# AlmosFinalMC.net
KiCad netlist of a schematic drawn in EAGLE
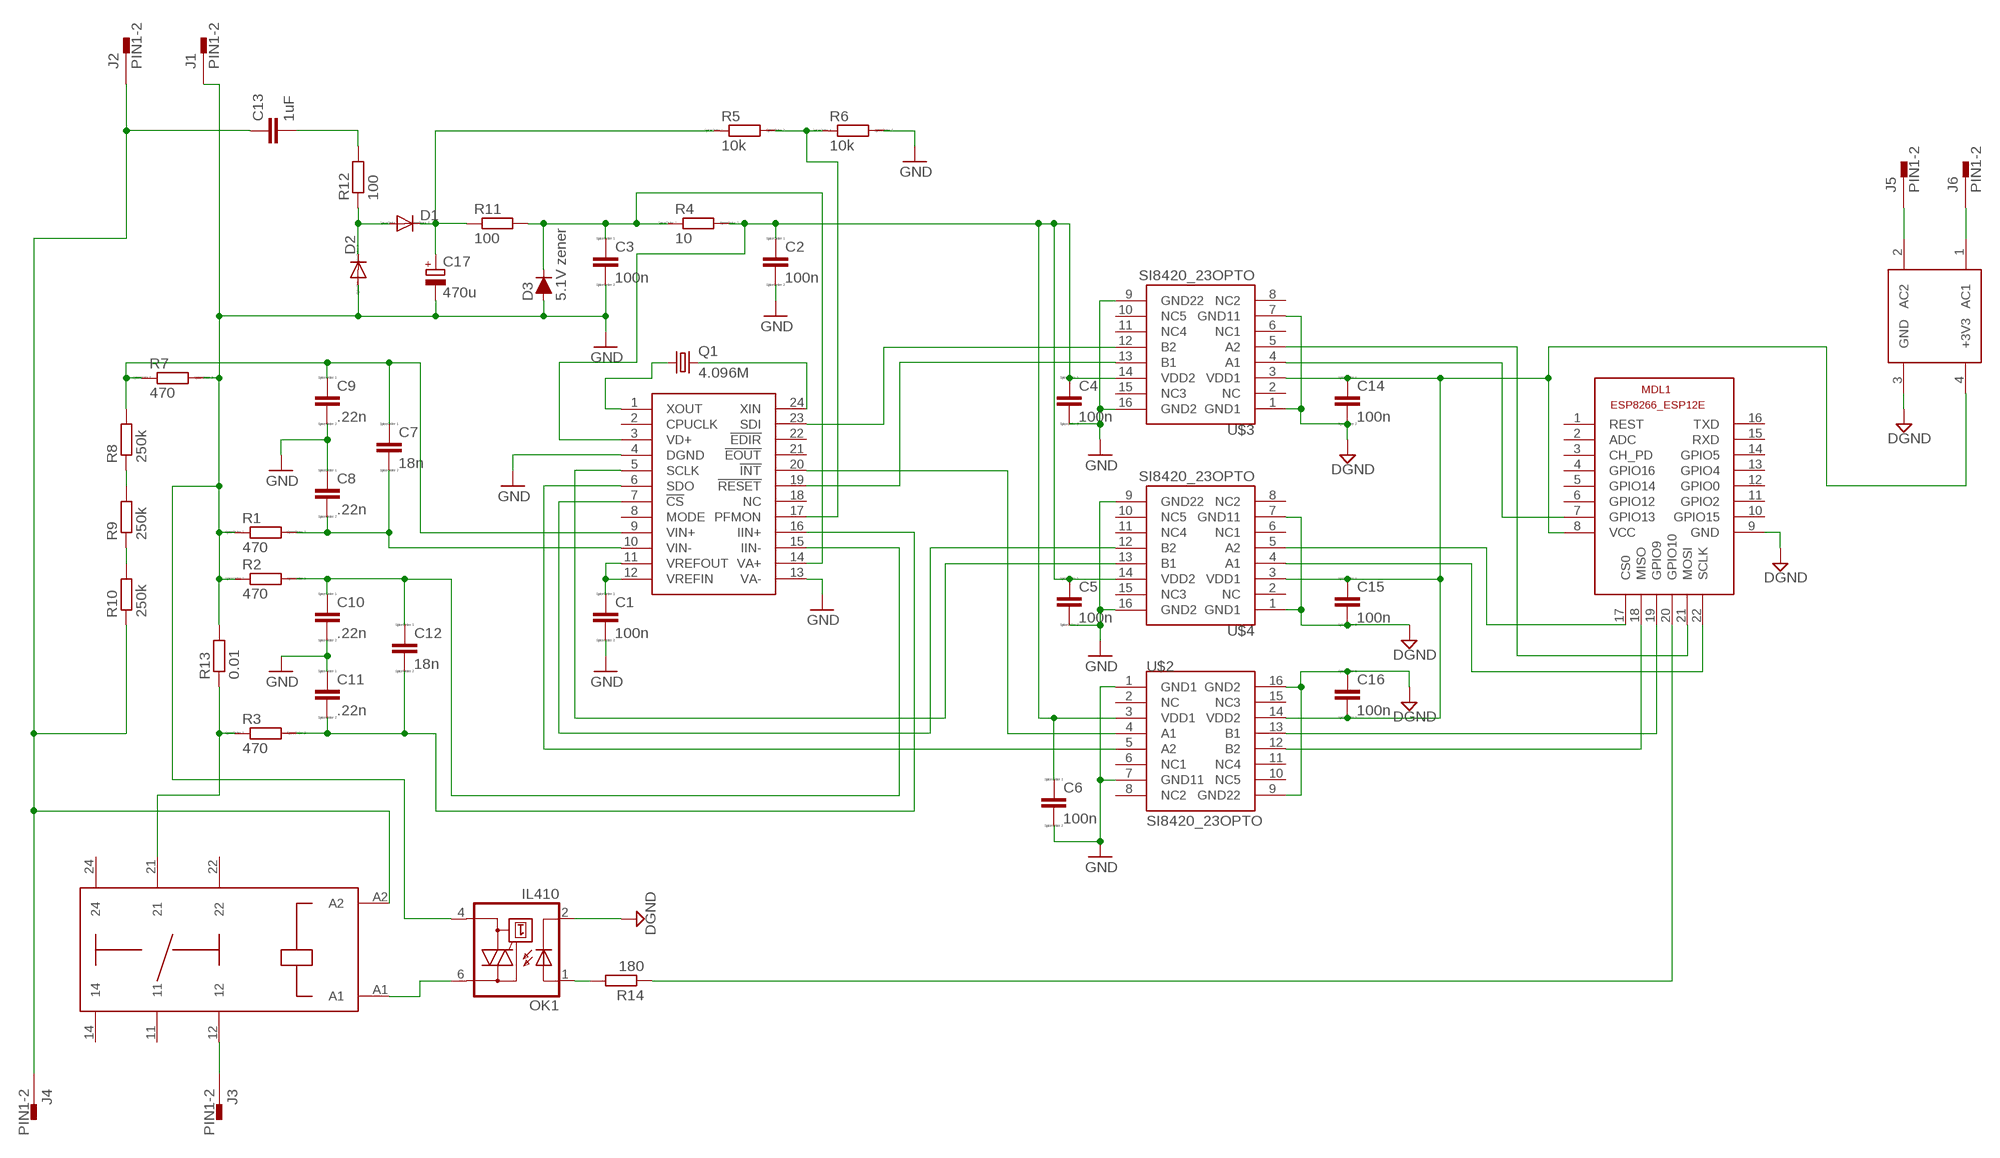
[diagram p0: schematic, sheet 1]

(export (version "E")
  (design (tool "Eeschema 10.0.6"))
  (components
    (comp (ref "C1")
      (value "100n")
      (footprint "eagle-import:C0805")
      (libsource (lib "eagle-import") (part "C"))
    )
    (comp (ref "C2")
      (value "100n")
      (footprint "eagle-import:C0805")
      (libsource (lib "eagle-import") (part "C"))
    )
    (comp (ref "C3")
      (value "100n")
      (footprint "eagle-import:C0805")
      (libsource (lib "eagle-import") (part "C"))
    )
    (comp (ref "C4")
      (value "100n")
      (footprint "eagle-import:C0805")
      (libsource (lib "eagle-import") (part "C"))
    )
    (comp (ref "C5")
      (value "100n")
      (footprint "eagle-import:C0805")
      (libsource (lib "eagle-import") (part "C"))
    )
    (comp (ref "C6")
      (value "100n")
      (footprint "eagle-import:C0805")
      (libsource (lib "eagle-import") (part "C"))
    )
    (comp (ref "C7")
      (value "18n")
      (footprint "eagle-import:C0805")
      (libsource (lib "eagle-import") (part "C"))
    )
    (comp (ref "C8")
      (value ".22n")
      (footprint "eagle-import:C0805")
      (libsource (lib "eagle-import") (part "C"))
    )
    (comp (ref "C9")
      (value ".22n")
      (footprint "eagle-import:C0805")
      (libsource (lib "eagle-import") (part "C"))
    )
    (comp (ref "C10")
      (value ".22n")
      (footprint "eagle-import:C0805")
      (libsource (lib "eagle-import") (part "C"))
    )
    (comp (ref "C11")
      (value ".22n")
      (footprint "eagle-import:C0805")
      (libsource (lib "eagle-import") (part "C"))
    )
    (comp (ref "C12")
      (value "18n")
      (footprint "eagle-import:C0805")
      (libsource (lib "eagle-import") (part "C"))
    )
    (comp (ref "C13")
      (value "1uF")
      (footprint "eagle-import:C225-113X268")
      (libsource (lib "eagle-import") (part "C-EU225-113X268"))
    )
    (comp (ref "C14")
      (value "100n")
      (footprint "eagle-import:C0805")
      (libsource (lib "eagle-import") (part "C"))
    )
    (comp (ref "C15")
      (value "100n")
      (footprint "eagle-import:C0805")
      (libsource (lib "eagle-import") (part "C"))
    )
    (comp (ref "C16")
      (value "100n")
      (footprint "eagle-import:C0805")
      (libsource (lib "eagle-import") (part "C"))
    )
    (comp (ref "C17")
      (value "470u")
      (footprint "eagle-import:PANASONIC_G")
      (libsource (lib "eagle-import") (part "CPOL-EUG"))
    )
    (comp (ref "D1")
      (value "DIODE-DO-214AC")
      (footprint "eagle-import:DO-214AC")
      (libsource (lib "eagle-import") (part "DIODE-DO-214AC"))
    )
    (comp (ref "D2")
      (value "DIODE-DO-214AC")
      (footprint "eagle-import:DO-214AC")
      (libsource (lib "eagle-import") (part "DIODE-DO-214AC"))
    )
    (comp (ref "D3")
      (value "5.1V zener")
      (footprint "eagle-import:SOD123")
      (libsource (lib "eagle-import") (part "D-FILL-SOD123"))
    )
    (comp (ref "J1")
      (value "PIN1-2")
      (footprint "eagle-import:62221")
      (fields (field (name "MF") "TYCO ELECTRONICS") (field (name "MPN") "62221-1"))
      (libsource (lib "eagle-import") (part "PIN1-2"))
    )
    (comp (ref "J2")
      (value "PIN1-2")
      (footprint "eagle-import:62221")
      (fields (field (name "MF") "TYCO ELECTRONICS") (field (name "MPN") "62221-1"))
      (libsource (lib "eagle-import") (part "PIN1-2"))
    )
    (comp (ref "J3")
      (value "PIN1-2")
      (footprint "eagle-import:62221")
      (fields (field (name "MF") "TYCO ELECTRONICS") (field (name "MPN") "62221-1"))
      (libsource (lib "eagle-import") (part "PIN1-2"))
    )
    (comp (ref "J4")
      (value "PIN1-2")
      (footprint "eagle-import:62221")
      (fields (field (name "MF") "TYCO ELECTRONICS") (field (name "MPN") "62221-1"))
      (libsource (lib "eagle-import") (part "PIN1-2"))
    )
    (comp (ref "J5")
      (value "PIN1-2")
      (footprint "eagle-import:62221")
      (fields (field (name "MF") "TYCO ELECTRONICS") (field (name "MPN") "62221-1"))
      (libsource (lib "eagle-import") (part "PIN1-2"))
    )
    (comp (ref "J6")
      (value "PIN1-2")
      (footprint "eagle-import:62221")
      (fields (field (name "MF") "TYCO ELECTRONICS") (field (name "MPN") "62221-1"))
      (libsource (lib "eagle-import") (part "PIN1-2"))
    )
    (comp (ref "MDL1")
      (value "ESP8266-12EESP8266-ESP12E")
      (footprint "eagle-import:ESP8266-ESP12E")
      (libsource (lib "eagle-import") (part "ESP8266-12EESP8266-ESP12E"))
    )
    (comp (ref "OK1")
      (value "IL410")
      (footprint "eagle-import:DIL06")
      (fields (field (name "MF") "VISHAY/TELEFUNKEN"))
      (libsource (lib "eagle-import") (part "IL410"))
    )
    (comp (ref "Q1")
      (value "4.096M")
      (footprint "eagle-import:HC49UP")
      (libsource (lib "eagle-import") (part "CRYSTALHC49UP"))
    )
    (comp (ref "R1")
      (value "470")
      (footprint "eagle-import:R0805")
      (libsource (lib "eagle-import") (part "R"))
    )
    (comp (ref "R2")
      (value "470")
      (footprint "eagle-import:R0805")
      (libsource (lib "eagle-import") (part "R"))
    )
    (comp (ref "R3")
      (value "470")
      (footprint "eagle-import:R0805")
      (libsource (lib "eagle-import") (part "R"))
    )
    (comp (ref "R4")
      (value "10")
      (footprint "eagle-import:R0805")
      (libsource (lib "eagle-import") (part "R"))
    )
    (comp (ref "R5")
      (value "10k")
      (footprint "eagle-import:R0805")
      (libsource (lib "eagle-import") (part "R"))
    )
    (comp (ref "R6")
      (value "10k")
      (footprint "eagle-import:R0805")
      (libsource (lib "eagle-import") (part "R"))
    )
    (comp (ref "R7")
      (value "470")
      (footprint "eagle-import:R0805")
      (libsource (lib "eagle-import") (part "R"))
    )
    (comp (ref "R8")
      (value "250k")
      (footprint "eagle-import:0204_5")
      (libsource (lib "eagle-import") (part "R-EU_0204/5"))
    )
    (comp (ref "R9")
      (value "250k")
      (footprint "eagle-import:0204_5")
      (libsource (lib "eagle-import") (part "R-EU_0204/5"))
    )
    (comp (ref "R10")
      (value "250k")
      (footprint "eagle-import:0204_5")
      (libsource (lib "eagle-import") (part "R-EU_0204/5"))
    )
    (comp (ref "R11")
      (value "100")
      (footprint "eagle-import:0207_5V")
      (libsource (lib "eagle-import") (part "R-EU_0207/5V"))
    )
    (comp (ref "R12")
      (value "100")
      (footprint "eagle-import:0309_10")
      (libsource (lib "eagle-import") (part "R-EU_0309/10"))
    )
    (comp (ref "R13")
      (value "0.01")
      (footprint "eagle-import:RDH_15")
      (libsource (lib "eagle-import") (part "R-EU_RDH/15"))
    )
    (comp (ref "R14")
      (value "180")
      (footprint "eagle-import:R0805")
      (libsource (lib "eagle-import") (part "R-EU_R0805"))
    )
    (comp (ref "U$1")
      (value "CS5460A")
      (footprint "eagle-import:SSOP24")
      (libsource (lib "eagle-import") (part "CS5460A"))
    )
    (comp (ref "U$2")
      (value "SI8420_23OPTO")
      (footprint "eagle-import:SI8420-SOIC8WB")
      (libsource (lib "eagle-import") (part "SI8420_23OPTO"))
    )
    (comp (ref "U$3")
      (value "SI8420_23OPTO")
      (footprint "eagle-import:SI8420-SOIC8WB")
      (libsource (lib "eagle-import") (part "SI8420_23OPTO"))
    )
    (comp (ref "U$4")
      (value "SI8420_23OPTO")
      (footprint "eagle-import:SI8420-SOIC8WB")
      (libsource (lib "eagle-import") (part "SI8420_23OPTO"))
    )
    (comp (ref "U$5")
      (value "RAC02")
      (footprint "eagle-import:RAC02")
      (libsource (lib "eagle-import") (part "RAC02"))
    )
    (comp (ref "U$6")
      (value "FINDER40-61")
      (footprint "eagle-import:FINDER40-61")
      (libsource (lib "eagle-import") (part "FINDER40-61"))
    )
  )
  (nets
    (net (code "1") (name "DGND") (class "Default")
      (node (ref "C14") (pin "2") (pinfunction "2_2") (pintype "passive"))
      (node (ref "C15") (pin "2") (pinfunction "2_2") (pintype "passive"))
      (node (ref "C16") (pin "1") (pinfunction "1_1") (pintype "passive"))
      (node (ref "MDL1") (pin "9") (pinfunction "GND_9") (pintype "bidirectional"))
      (node (ref "OK1") (pin "2") (pinfunction "C_2") (pintype "passive"))
      (node (ref "U$2") (pin "16") (pinfunction "GND2_16") (pintype "bidirectional"))
      (node (ref "U$2") (pin "9") (pinfunction "GND22_9") (pintype "bidirectional"))
      (node (ref "U$3") (pin "1") (pinfunction "GND1_1") (pintype "bidirectional"))
      (node (ref "U$3") (pin "7") (pinfunction "GND11_7") (pintype "bidirectional"))
      (node (ref "U$4") (pin "1") (pinfunction "GND1_1") (pintype "bidirectional"))
      (node (ref "U$4") (pin "7") (pinfunction "GND11_7") (pintype "bidirectional"))
      (node (ref "U$5") (pin "3") (pinfunction "GND_3") (pintype "bidirectional"))
    )
    (net (code "2") (name "GND") (class "Default")
      (node (ref "C1") (pin "2") (pinfunction "2_2") (pintype "passive"))
      (node (ref "C10") (pin "2") (pinfunction "2_2") (pintype "passive"))
      (node (ref "C11") (pin "1") (pinfunction "1_1") (pintype "passive"))
      (node (ref "C17") (pin "-") (pinfunction "-_-") (pintype "passive"))
      (node (ref "C2") (pin "2") (pinfunction "2_2") (pintype "passive"))
      (node (ref "C3") (pin "2") (pinfunction "2_2") (pintype "passive"))
      (node (ref "C4") (pin "2") (pinfunction "2_2") (pintype "passive"))
      (node (ref "C5") (pin "2") (pinfunction "2_2") (pintype "passive"))
      (node (ref "C6") (pin "2") (pinfunction "2_2") (pintype "passive"))
      (node (ref "C8") (pin "1") (pinfunction "1_1") (pintype "passive"))
      (node (ref "C9") (pin "2") (pinfunction "2_2") (pintype "passive"))
      (node (ref "D2") (pin "A") (pinfunction "A_A") (pintype "passive"))
      (node (ref "D3") (pin "2") (pinfunction "A_2") (pintype "passive"))
      (node (ref "J1") (pin "1") (pinfunction "1_1") (pintype "passive"))
      (node (ref "OK1") (pin "4") (pinfunction "A1_4") (pintype "passive"))
      (node (ref "R1") (pin "1") (pinfunction "1_1") (pintype "passive"))
      (node (ref "R13") (pin "2") (pinfunction "2_2") (pintype "passive"))
      (node (ref "R2") (pin "1") (pinfunction "1_1") (pintype "passive"))
      (node (ref "R6") (pin "2") (pinfunction "2_2") (pintype "passive"))
      (node (ref "R7") (pin "2") (pinfunction "2_2") (pintype "passive"))
      (node (ref "U$1") (pin "13") (pinfunction "VA-_13") (pintype "bidirectional"))
      (node (ref "U$1") (pin "4") (pinfunction "DGND_4") (pintype "bidirectional"))
      (node (ref "U$2") (pin "1") (pinfunction "GND1_1") (pintype "bidirectional"))
      (node (ref "U$2") (pin "7") (pinfunction "GND11_7") (pintype "bidirectional"))
      (node (ref "U$3") (pin "16") (pinfunction "GND2_16") (pintype "bidirectional"))
      (node (ref "U$3") (pin "9") (pinfunction "GND22_9") (pintype "bidirectional"))
      (node (ref "U$4") (pin "16") (pinfunction "GND2_16") (pintype "bidirectional"))
      (node (ref "U$4") (pin "9") (pinfunction "GND22_9") (pintype "bidirectional"))
    )
    (net (code "3") (name "Net-(C13-Pad1)") (class "Default")
      (node (ref "C13") (pin "1") (pinfunction "1_1") (pintype "passive"))
      (node (ref "J2") (pin "1") (pinfunction "1_1") (pintype "passive"))
      (node (ref "J4") (pin "1") (pinfunction "1_1") (pintype "passive"))
      (node (ref "R10") (pin "1") (pinfunction "1_1") (pintype "passive"))
      (node (ref "U$6") (pin "A2") (pinfunction "A2_A2") (pintype "bidirectional"))
    )
    (net (code "4") (name "Net-(C13-Pad2)") (class "Default")
      (node (ref "C13") (pin "2") (pinfunction "2_2") (pintype "passive"))
      (node (ref "R12") (pin "2") (pinfunction "2_2") (pintype "passive"))
    )
    (net (code "5") (name "Net-(C17-Pad+)") (class "Default")
      (node (ref "C17") (pin "+") (pinfunction "+_+") (pintype "passive"))
      (node (ref "D1") (pin "C") (pinfunction "C_C") (pintype "passive"))
      (node (ref "R11") (pin "1") (pinfunction "1_1") (pintype "passive"))
      (node (ref "R5") (pin "1") (pinfunction "1_1") (pintype "passive"))
    )
    (net (code "6") (name "Net-(D1-PadA)") (class "Default")
      (node (ref "D1") (pin "A") (pinfunction "A_A") (pintype "passive"))
      (node (ref "D2") (pin "C") (pinfunction "C_C") (pintype "passive"))
      (node (ref "R12") (pin "1") (pinfunction "1_1") (pintype "passive"))
    )
    (net (code "7") (name "Net-(D3-C)") (class "Default")
      (node (ref "C3") (pin "1") (pinfunction "1_1") (pintype "passive"))
      (node (ref "D3") (pin "1") (pinfunction "C_1") (pintype "passive"))
      (node (ref "R11") (pin "2") (pinfunction "2_2") (pintype "passive"))
      (node (ref "R4") (pin "1") (pinfunction "1_1") (pintype "passive"))
      (node (ref "U$1") (pin "14") (pinfunction "VA+_14") (pintype "bidirectional"))
    )
    (net (code "8") (name "Net-(J3-Pad1)") (class "Default")
      (node (ref "J3") (pin "1") (pinfunction "1_1") (pintype "passive"))
      (node (ref "U$6") (pin "12") (pinfunction "12_12") (pintype "bidirectional"))
    )
    (net (code "9") (name "Net-(MDL1-CS0)") (class "Default")
      (node (ref "MDL1") (pin "17") (pinfunction "CS0_17") (pintype "bidirectional"))
      (node (ref "U$4") (pin "5") (pinfunction "A2_5") (pintype "bidirectional"))
    )
    (net (code "10") (name "Net-(MDL1-GPIO9)") (class "Default")
      (node (ref "MDL1") (pin "19") (pinfunction "GPIO9_19") (pintype "bidirectional"))
      (node (ref "U$2") (pin "13") (pinfunction "B1_13") (pintype "bidirectional"))
    )
    (net (code "11") (name "Net-(MDL1-GPIO10)") (class "Default")
      (node (ref "MDL1") (pin "20") (pinfunction "GPIO10_20") (pintype "bidirectional"))
      (node (ref "R14") (pin "1") (pinfunction "1_1") (pintype "passive"))
    )
    (net (code "12") (name "Net-(MDL1-GPIO13)") (class "Default")
      (node (ref "MDL1") (pin "7") (pinfunction "GPIO13_7") (pintype "bidirectional"))
      (node (ref "U$3") (pin "4") (pinfunction "A1_4") (pintype "bidirectional"))
    )
    (net (code "13") (name "Net-(MDL1-MISO)") (class "Default")
      (node (ref "MDL1") (pin "18") (pinfunction "MISO_18") (pintype "bidirectional"))
      (node (ref "U$2") (pin "12") (pinfunction "B2_12") (pintype "bidirectional"))
    )
    (net (code "14") (name "Net-(MDL1-MOSI)") (class "Default")
      (node (ref "MDL1") (pin "21") (pinfunction "MOSI_21") (pintype "bidirectional"))
      (node (ref "U$3") (pin "5") (pinfunction "A2_5") (pintype "bidirectional"))
    )
    (net (code "15") (name "Net-(MDL1-SCLK)") (class "Default")
      (node (ref "MDL1") (pin "22") (pinfunction "SCLK_22") (pintype "bidirectional"))
      (node (ref "U$4") (pin "4") (pinfunction "A1_4") (pintype "bidirectional"))
    )
    (net (code "16") (name "Net-(MDL1-VCC)") (class "Default")
      (node (ref "C14") (pin "1") (pinfunction "1_1") (pintype "passive"))
      (node (ref "C15") (pin "1") (pinfunction "1_1") (pintype "passive"))
      (node (ref "C16") (pin "2") (pinfunction "2_2") (pintype "passive"))
      (node (ref "MDL1") (pin "8") (pinfunction "VCC_8") (pintype "bidirectional"))
      (node (ref "U$2") (pin "14") (pinfunction "VDD2_14") (pintype "bidirectional"))
      (node (ref "U$3") (pin "3") (pinfunction "VDD1_3") (pintype "bidirectional"))
      (node (ref "U$4") (pin "3") (pinfunction "VDD1_3") (pintype "bidirectional"))
      (node (ref "U$5") (pin "4") (pinfunction "+3V3_4") (pintype "bidirectional"))
    )
    (net (code "17") (name "Net-(OK1-A)") (class "Default")
      (node (ref "OK1") (pin "1") (pinfunction "A_1") (pintype "passive"))
      (node (ref "R14") (pin "2") (pinfunction "2_2") (pintype "passive"))
    )
    (net (code "18") (name "Net-(OK1-A2)") (class "Default")
      (node (ref "OK1") (pin "6") (pinfunction "A2_6") (pintype "passive"))
      (node (ref "U$6") (pin "A1") (pinfunction "A1_A1") (pintype "bidirectional"))
    )
    (net (code "19") (name "Net-(R8-Pad1)") (class "Default")
      (node (ref "R8") (pin "1") (pinfunction "1_1") (pintype "passive"))
      (node (ref "R9") (pin "2") (pinfunction "2_2") (pintype "passive"))
    )
    (net (code "20") (name "Net-(R10-Pad2)") (class "Default")
      (node (ref "R10") (pin "2") (pinfunction "2_2") (pintype "passive"))
      (node (ref "R9") (pin "1") (pinfunction "1_1") (pintype "passive"))
    )
    (net (code "21") (name "Net-(R13-Pad1)") (class "Default")
      (node (ref "R13") (pin "1") (pinfunction "1_1") (pintype "passive"))
      (node (ref "R3") (pin "1") (pinfunction "1_1") (pintype "passive"))
      (node (ref "U$6") (pin "21") (pinfunction "21_21") (pintype "bidirectional"))
    )
    (net (code "22") (name "Net-(U$1-IIN+)") (class "Default")
      (node (ref "C11") (pin "2") (pinfunction "2_2") (pintype "passive"))
      (node (ref "C12") (pin "2") (pinfunction "2_2") (pintype "passive"))
      (node (ref "R3") (pin "2") (pinfunction "2_2") (pintype "passive"))
      (node (ref "U$1") (pin "16") (pinfunction "IIN+_16") (pintype "bidirectional"))
    )
    (net (code "23") (name "Net-(U$1-IIN-)") (class "Default")
      (node (ref "C10") (pin "1") (pinfunction "1_1") (pintype "passive"))
      (node (ref "C12") (pin "1") (pinfunction "1_1") (pintype "passive"))
      (node (ref "R2") (pin "2") (pinfunction "2_2") (pintype "passive"))
      (node (ref "U$1") (pin "15") (pinfunction "IIN-_15") (pintype "bidirectional"))
    )
    (net (code "24") (name "Net-(U$1-PFMON)") (class "Default")
      (node (ref "R5") (pin "2") (pinfunction "2_2") (pintype "passive"))
      (node (ref "R6") (pin "1") (pinfunction "1_1") (pintype "passive"))
      (node (ref "U$1") (pin "17") (pinfunction "PFMON_17") (pintype "bidirectional"))
    )
    (net (code "25") (name "Net-(U$1-SCLK)") (class "Default")
      (node (ref "U$1") (pin "5") (pinfunction "SCLK_5") (pintype "bidirectional"))
      (node (ref "U$4") (pin "13") (pinfunction "B1_13") (pintype "bidirectional"))
    )
    (net (code "26") (name "Net-(U$1-SDI)") (class "Default")
      (node (ref "U$1") (pin "23") (pinfunction "SDI_23") (pintype "bidirectional"))
      (node (ref "U$3") (pin "12") (pinfunction "B2_12") (pintype "bidirectional"))
    )
    (net (code "27") (name "Net-(U$1-SDO)") (class "Default")
      (node (ref "U$1") (pin "6") (pinfunction "SDO_6") (pintype "bidirectional"))
      (node (ref "U$2") (pin "5") (pinfunction "A2_5") (pintype "bidirectional"))
    )
    (net (code "28") (name "Net-(U$1-VD+)") (class "Default")
      (node (ref "C2") (pin "1") (pinfunction "1_1") (pintype "passive"))
      (node (ref "C4") (pin "1") (pinfunction "1_1") (pintype "passive"))
      (node (ref "C5") (pin "1") (pinfunction "1_1") (pintype "passive"))
      (node (ref "C6") (pin "1") (pinfunction "1_1") (pintype "passive"))
      (node (ref "R4") (pin "2") (pinfunction "2_2") (pintype "passive"))
      (node (ref "U$1") (pin "3") (pinfunction "VD+_3") (pintype "bidirectional"))
      (node (ref "U$2") (pin "3") (pinfunction "VDD1_3") (pintype "bidirectional"))
      (node (ref "U$3") (pin "14") (pinfunction "VDD2_14") (pintype "bidirectional"))
      (node (ref "U$4") (pin "14") (pinfunction "VDD2_14") (pintype "bidirectional"))
    )
    (net (code "29") (name "Net-(U$1-VIN+)") (class "Default")
      (node (ref "C7") (pin "1") (pinfunction "1_1") (pintype "passive"))
      (node (ref "C9") (pin "1") (pinfunction "1_1") (pintype "passive"))
      (node (ref "R7") (pin "1") (pinfunction "1_1") (pintype "passive"))
      (node (ref "R8") (pin "2") (pinfunction "2_2") (pintype "passive"))
      (node (ref "U$1") (pin "9") (pinfunction "VIN+_9") (pintype "bidirectional"))
    )
    (net (code "30") (name "Net-(U$1-VIN-)") (class "Default")
      (node (ref "C7") (pin "2") (pinfunction "2_2") (pintype "passive"))
      (node (ref "C8") (pin "2") (pinfunction "2_2") (pintype "passive"))
      (node (ref "R1") (pin "2") (pinfunction "2_2") (pintype "passive"))
      (node (ref "U$1") (pin "10") (pinfunction "VIN-_10") (pintype "bidirectional"))
    )
    (net (code "31") (name "Net-(U$1-VREFIN)") (class "Default")
      (node (ref "C1") (pin "1") (pinfunction "1_1") (pintype "passive"))
      (node (ref "U$1") (pin "11") (pinfunction "VREFOUT_11") (pintype "bidirectional"))
      (node (ref "U$1") (pin "12") (pinfunction "VREFIN_12") (pintype "bidirectional"))
    )
    (net (code "32") (name "Net-(U$1-XIN)") (class "Default")
      (node (ref "Q1") (pin "2") (pinfunction "2_2") (pintype "passive"))
      (node (ref "U$1") (pin "24") (pinfunction "XIN_24") (pintype "bidirectional"))
    )
    (net (code "33") (name "Net-(U$1-XOUT)") (class "Default")
      (node (ref "Q1") (pin "1") (pinfunction "1_1") (pintype "passive"))
      (node (ref "U$1") (pin "1") (pinfunction "XOUT_1") (pintype "bidirectional"))
    )
    (net (code "34") (name "Net-(U$1-~{CS})") (class "Default")
      (node (ref "U$1") (pin "7") (pinfunction "~{CS}_7") (pintype "bidirectional"))
      (node (ref "U$4") (pin "12") (pinfunction "B2_12") (pintype "bidirectional"))
    )
    (net (code "35") (name "Net-(U$1-~{INT})") (class "Default")
      (node (ref "U$1") (pin "20") (pinfunction "~{INT}_20") (pintype "bidirectional"))
      (node (ref "U$2") (pin "4") (pinfunction "A1_4") (pintype "bidirectional"))
    )
    (net (code "36") (name "Net-(U$1-~{RESET})") (class "Default")
      (node (ref "U$1") (pin "19") (pinfunction "~{RESET}_19") (pintype "bidirectional"))
      (node (ref "U$3") (pin "13") (pinfunction "B1_13") (pintype "bidirectional"))
    )
    (net (code "37") (name "Net-(U$5-AC1)") (class "Default")
      (node (ref "J6") (pin "1") (pinfunction "1_1") (pintype "passive"))
      (node (ref "U$5") (pin "1") (pinfunction "AC1_1") (pintype "bidirectional"))
    )
    (net (code "38") (name "Net-(U$5-AC2)") (class "Default")
      (node (ref "J5") (pin "1") (pinfunction "1_1") (pintype "passive"))
      (node (ref "U$5") (pin "2") (pinfunction "AC2_2") (pintype "bidirectional"))
    )
    (net (code "39") (name "unconnected-(MDL1-ADC-Pad2)") (class "Default")
      (node (ref "MDL1") (pin "2") (pinfunction "ADC_2") (pintype "bidirectional"))
    )
    (net (code "40") (name "unconnected-(MDL1-CH_PD-Pad3)") (class "Default")
      (node (ref "MDL1") (pin "3") (pinfunction "CH_PD_3") (pintype "bidirectional"))
    )
    (net (code "41") (name "unconnected-(MDL1-GPIO0-Pad12)") (class "Default")
      (node (ref "MDL1") (pin "12") (pinfunction "GPIO0_12") (pintype "bidirectional"))
    )
    (net (code "42") (name "unconnected-(MDL1-GPIO2-Pad11)") (class "Default")
      (node (ref "MDL1") (pin "11") (pinfunction "GPIO2_11") (pintype "bidirectional"))
    )
    (net (code "43") (name "unconnected-(MDL1-GPIO4-Pad13)") (class "Default")
      (node (ref "MDL1") (pin "13") (pinfunction "GPIO4_13") (pintype "bidirectional"))
    )
    (net (code "44") (name "unconnected-(MDL1-GPIO5-Pad14)") (class "Default")
      (node (ref "MDL1") (pin "14") (pinfunction "GPIO5_14") (pintype "bidirectional"))
    )
    (net (code "45") (name "unconnected-(MDL1-GPIO12-Pad6)") (class "Default")
      (node (ref "MDL1") (pin "6") (pinfunction "GPIO12_6") (pintype "bidirectional"))
    )
    (net (code "46") (name "unconnected-(MDL1-GPIO14-Pad5)") (class "Default")
      (node (ref "MDL1") (pin "5") (pinfunction "GPIO14_5") (pintype "bidirectional"))
    )
    (net (code "47") (name "unconnected-(MDL1-GPIO15-Pad10)") (class "Default")
      (node (ref "MDL1") (pin "10") (pinfunction "GPIO15_10") (pintype "bidirectional"))
    )
    (net (code "48") (name "unconnected-(MDL1-GPIO16-Pad4)") (class "Default")
      (node (ref "MDL1") (pin "4") (pinfunction "GPIO16_4") (pintype "bidirectional"))
    )
    (net (code "49") (name "unconnected-(MDL1-REST-Pad1)") (class "Default")
      (node (ref "MDL1") (pin "1") (pinfunction "REST_1") (pintype "bidirectional"))
    )
    (net (code "50") (name "unconnected-(MDL1-RXD-Pad15)") (class "Default")
      (node (ref "MDL1") (pin "15") (pinfunction "RXD_15") (pintype "bidirectional"))
    )
    (net (code "51") (name "unconnected-(MDL1-TXD-Pad16)") (class "Default")
      (node (ref "MDL1") (pin "16") (pinfunction "TXD_16") (pintype "bidirectional"))
    )
    (net (code "52") (name "unconnected-(U$1-CPUCLK-Pad2)") (class "Default")
      (node (ref "U$1") (pin "2") (pinfunction "CPUCLK_2") (pintype "bidirectional"))
    )
    (net (code "53") (name "unconnected-(U$1-MODE-Pad8)") (class "Default")
      (node (ref "U$1") (pin "8") (pinfunction "MODE_8") (pintype "bidirectional"))
    )
    (net (code "54") (name "unconnected-(U$1-NC-Pad18)") (class "Default")
      (node (ref "U$1") (pin "18") (pinfunction "NC_18") (pintype "bidirectional"))
    )
    (net (code "55") (name "unconnected-(U$1-~{EDIR}-Pad22)") (class "Default")
      (node (ref "U$1") (pin "22") (pinfunction "~{EDIR}_22") (pintype "bidirectional"))
    )
    (net (code "56") (name "unconnected-(U$1-~{EOUT}-Pad21)") (class "Default")
      (node (ref "U$1") (pin "21") (pinfunction "~{EOUT}_21") (pintype "bidirectional"))
    )
    (net (code "57") (name "unconnected-(U$2-NC-Pad2)") (class "Default")
      (node (ref "U$2") (pin "2") (pinfunction "NC_2") (pintype "no_connect"))
    )
    (net (code "58") (name "unconnected-(U$2-NC1-Pad6)") (class "Default")
      (node (ref "U$2") (pin "6") (pinfunction "NC1_6") (pintype "bidirectional"))
    )
    (net (code "59") (name "unconnected-(U$2-NC2-Pad8)") (class "Default")
      (node (ref "U$2") (pin "8") (pinfunction "NC2_8") (pintype "bidirectional"))
    )
    (net (code "60") (name "unconnected-(U$2-NC3-Pad15)") (class "Default")
      (node (ref "U$2") (pin "15") (pinfunction "NC3_15") (pintype "bidirectional"))
    )
    (net (code "61") (name "unconnected-(U$2-NC4-Pad11)") (class "Default")
      (node (ref "U$2") (pin "11") (pinfunction "NC4_11") (pintype "bidirectional"))
    )
    (net (code "62") (name "unconnected-(U$2-NC5-Pad10)") (class "Default")
      (node (ref "U$2") (pin "10") (pinfunction "NC5_10") (pintype "bidirectional"))
    )
    (net (code "63") (name "unconnected-(U$3-NC-Pad2)") (class "Default")
      (node (ref "U$3") (pin "2") (pinfunction "NC_2") (pintype "no_connect"))
    )
    (net (code "64") (name "unconnected-(U$3-NC1-Pad6)") (class "Default")
      (node (ref "U$3") (pin "6") (pinfunction "NC1_6") (pintype "bidirectional"))
    )
    (net (code "65") (name "unconnected-(U$3-NC2-Pad8)") (class "Default")
      (node (ref "U$3") (pin "8") (pinfunction "NC2_8") (pintype "bidirectional"))
    )
    (net (code "66") (name "unconnected-(U$3-NC3-Pad15)") (class "Default")
      (node (ref "U$3") (pin "15") (pinfunction "NC3_15") (pintype "bidirectional"))
    )
    (net (code "67") (name "unconnected-(U$3-NC4-Pad11)") (class "Default")
      (node (ref "U$3") (pin "11") (pinfunction "NC4_11") (pintype "bidirectional"))
    )
    (net (code "68") (name "unconnected-(U$3-NC5-Pad10)") (class "Default")
      (node (ref "U$3") (pin "10") (pinfunction "NC5_10") (pintype "bidirectional"))
    )
    (net (code "69") (name "unconnected-(U$4-NC-Pad2)") (class "Default")
      (node (ref "U$4") (pin "2") (pinfunction "NC_2") (pintype "no_connect"))
    )
    (net (code "70") (name "unconnected-(U$4-NC1-Pad6)") (class "Default")
      (node (ref "U$4") (pin "6") (pinfunction "NC1_6") (pintype "bidirectional"))
    )
    (net (code "71") (name "unconnected-(U$4-NC2-Pad8)") (class "Default")
      (node (ref "U$4") (pin "8") (pinfunction "NC2_8") (pintype "bidirectional"))
    )
    (net (code "72") (name "unconnected-(U$4-NC3-Pad15)") (class "Default")
      (node (ref "U$4") (pin "15") (pinfunction "NC3_15") (pintype "bidirectional"))
    )
    (net (code "73") (name "unconnected-(U$4-NC4-Pad11)") (class "Default")
      (node (ref "U$4") (pin "11") (pinfunction "NC4_11") (pintype "bidirectional"))
    )
    (net (code "74") (name "unconnected-(U$4-NC5-Pad10)") (class "Default")
      (node (ref "U$4") (pin "10") (pinfunction "NC5_10") (pintype "bidirectional"))
    )
    (net (code "75") (name "unconnected-(U$6-Pad11)") (class "Default")
      (node (ref "U$6") (pin "11") (pinfunction "11_11") (pintype "bidirectional"))
    )
    (net (code "76") (name "unconnected-(U$6-Pad14)") (class "Default")
      (node (ref "U$6") (pin "14") (pinfunction "14_14") (pintype "bidirectional"))
    )
    (net (code "77") (name "unconnected-(U$6-Pad22)") (class "Default")
      (node (ref "U$6") (pin "22") (pinfunction "22_22") (pintype "bidirectional"))
    )
    (net (code "78") (name "unconnected-(U$6-Pad24)") (class "Default")
      (node (ref "U$6") (pin "24") (pinfunction "24_24") (pintype "bidirectional"))
    )
  )
)
